# rotaryEncoder.net
KiCad netlist of a schematic drawn in Altium Designer
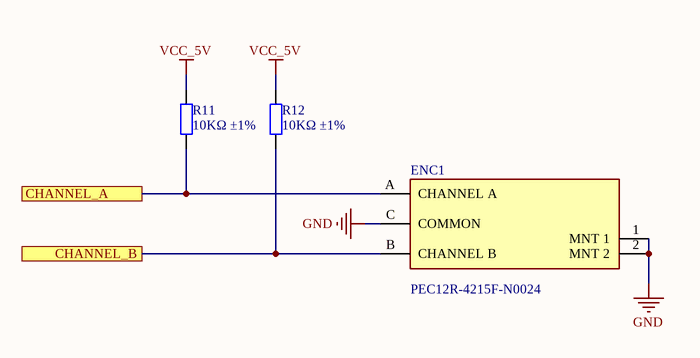
[diagram p0: rotaryEncoder.SchDoc]

(export (version "E")
  (design (tool "Eeschema 10.0.6"))
  (components
    (comp (ref "ENC1")
      (value "PEC12R-4215F-N0024")
      (footprint "FP-PEC12R-4215F-N0024-MFG")
      (description "ROTARY ENCODER")
      (libsource (lib "Altium Content Vault") (part "29c470f7ccee8b15657efb0c94ebc83"))
    )
    (comp (ref "R11")
      (value "10KΩ ±1%")
      (footprint "0603_R")
      (description "Chip resistor")
      (fields (field (name "MANUFACTURER") "Uniroyal Elec") (field (name "PARTNUMBER") "0603WAF1002T5E"))
      (libsource (lib "RES") (part "0603 10K (1002) 1%"))
    )
    (comp (ref "R12")
      (value "10KΩ ±1%")
      (footprint "0603_R")
      (description "Chip resistor")
      (fields (field (name "MANUFACTURER") "Uniroyal Elec") (field (name "PARTNUMBER") "0603WAF1002T5E"))
      (libsource (lib "RES") (part "0603 10K (1002) 1%"))
    )
  )
  (nets
    (net (code "1") (name "/CHANNEL_A") (class "Default")
      (node (ref "ENC1") (pin "A") (pinfunction "CHANNEL_A_A") (pintype "passive"))
      (node (ref "R11") (pin "2") (pinfunction "2_2") (pintype "passive"))
    )
    (net (code "2") (name "/CHANNEL_B") (class "Default")
      (node (ref "ENC1") (pin "B") (pinfunction "CHANNEL_B_B") (pintype "passive"))
      (node (ref "R12") (pin "2") (pinfunction "2_2") (pintype "passive"))
    )
    (net (code "3") (name "GND") (class "Default")
      (node (ref "ENC1") (pin "1") (pinfunction "MNT_1_1") (pintype "passive"))
      (node (ref "ENC1") (pin "2") (pinfunction "MNT_2_2") (pintype "passive"))
      (node (ref "ENC1") (pin "C") (pinfunction "COMMON_C") (pintype "passive"))
    )
    (net (code "4") (name "VCC_5V") (class "Default")
      (node (ref "R11") (pin "1") (pinfunction "1_1") (pintype "passive"))
      (node (ref "R12") (pin "1") (pinfunction "1_1") (pintype "passive"))
    )
  )
)
